# radiationsensor_r0.net
KiCad netlist of a schematic drawn in EAGLE
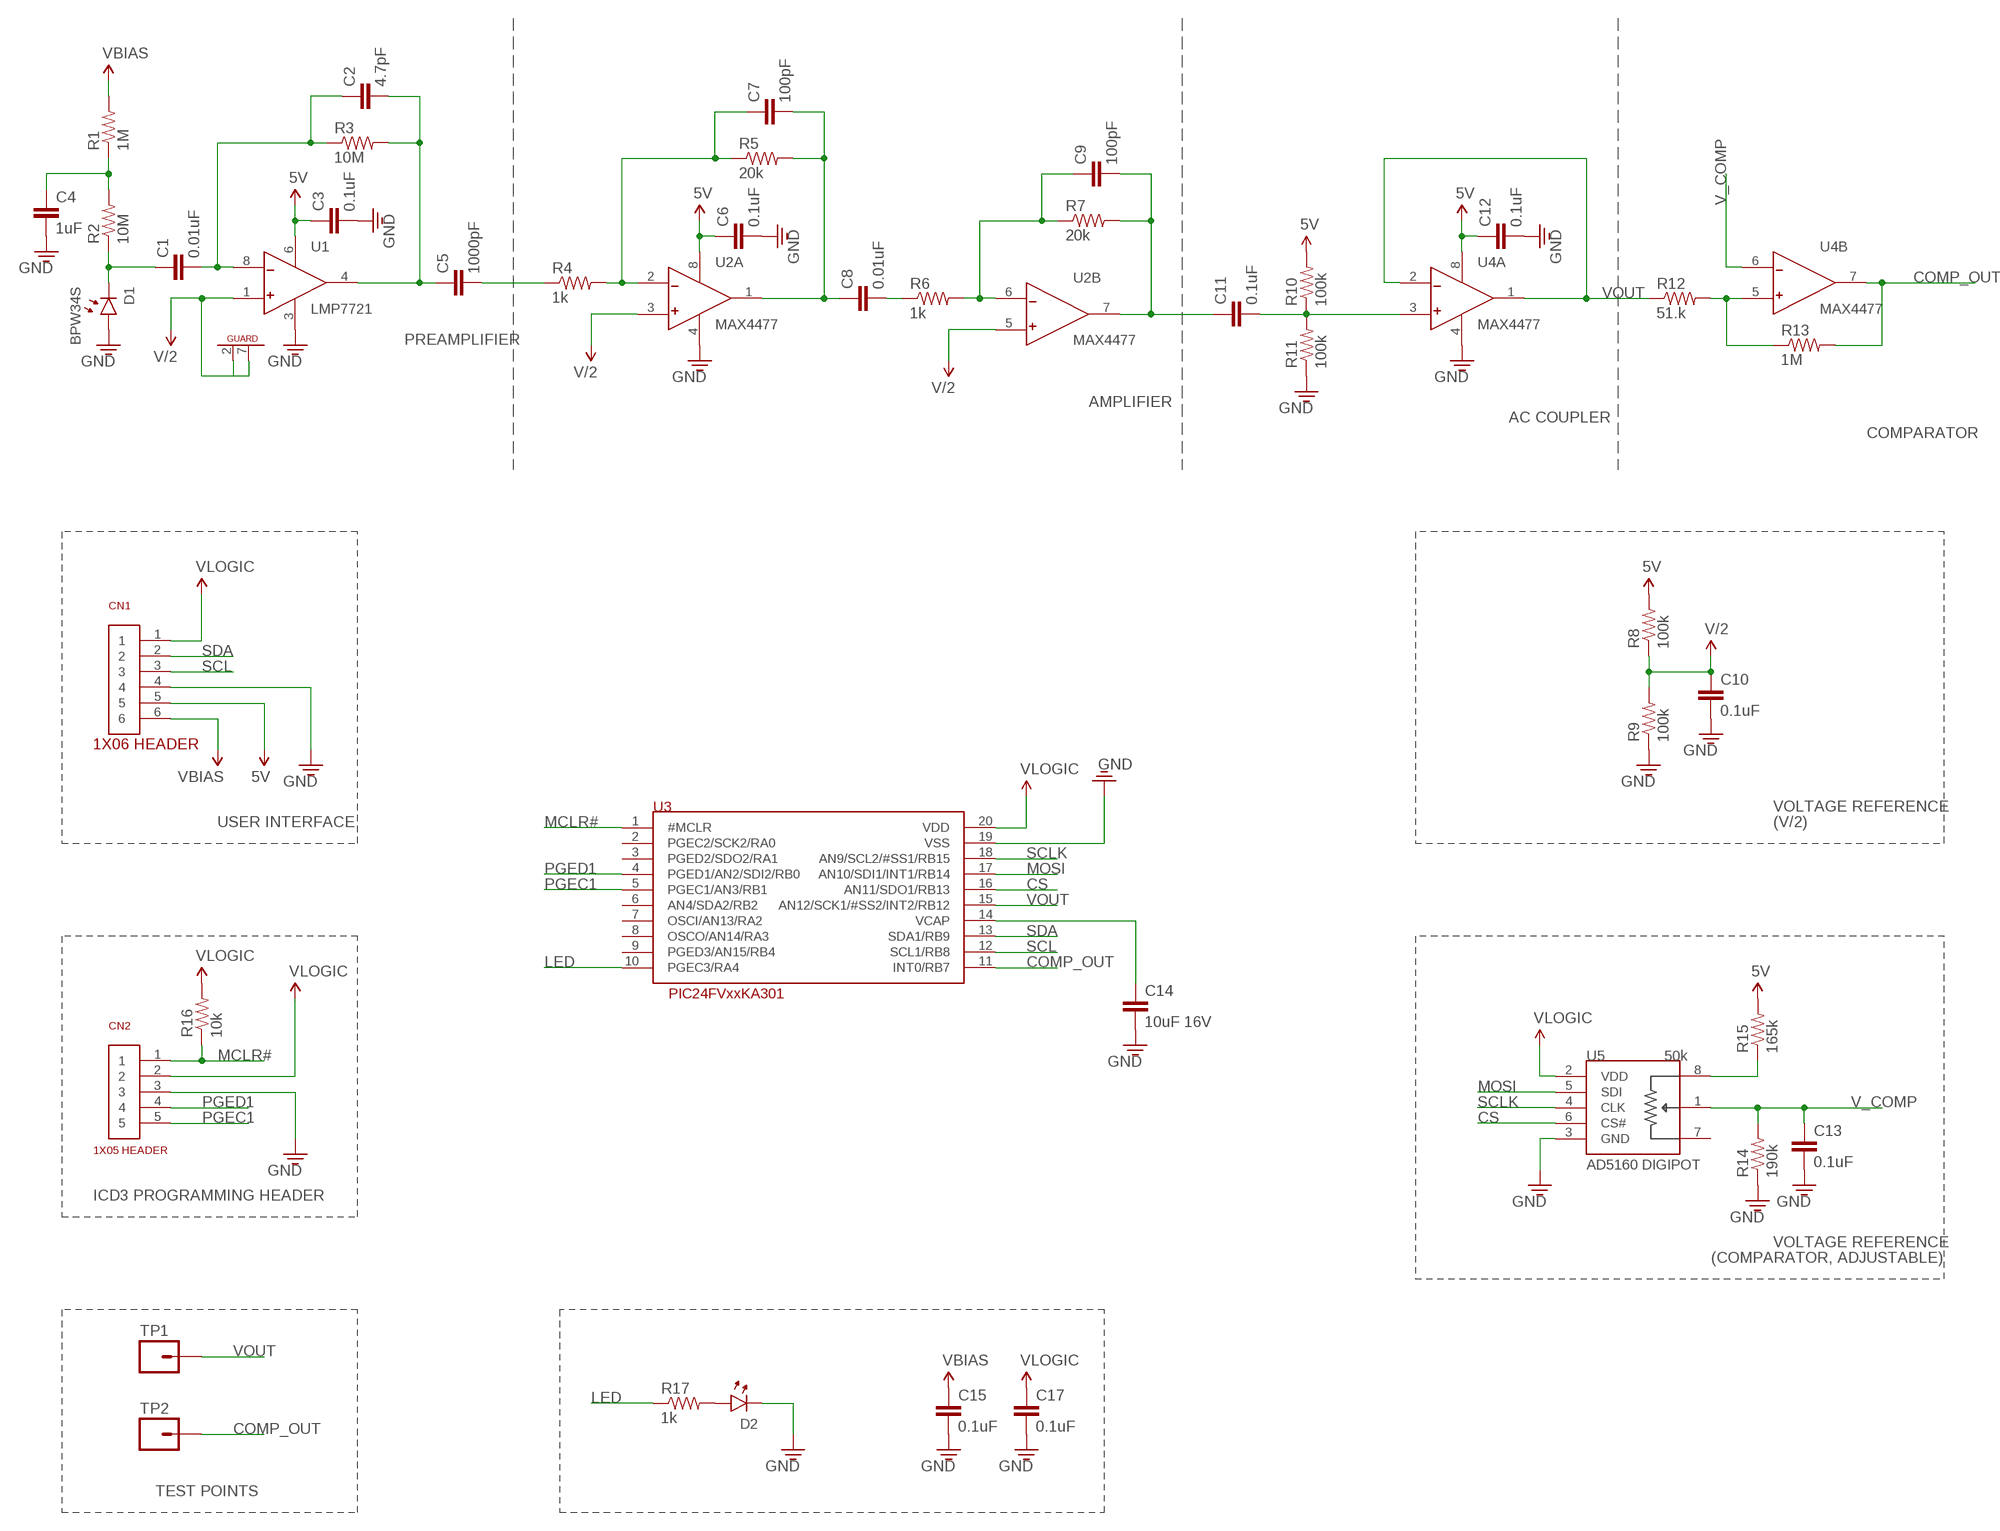
[diagram p0: schematic, sheet 1]

(export (version "E")
  (design (tool "Eeschema 10.0.6"))
  (components
    (comp (ref "C1")
      (value "0.01uF")
      (footprint "eagle-import:0603")
      (libsource (lib "eagle-import") (part "CAP0603"))
    )
    (comp (ref "C2")
      (value "4.7pF")
      (footprint "eagle-import:0603")
      (libsource (lib "eagle-import") (part "CAP0603"))
    )
    (comp (ref "C3")
      (value "0.1uF")
      (footprint "eagle-import:0603")
      (libsource (lib "eagle-import") (part "CAP0603"))
    )
    (comp (ref "C4")
      (value "1uF")
      (footprint "eagle-import:0603")
      (libsource (lib "eagle-import") (part "CAP0603"))
    )
    (comp (ref "C5")
      (value "1000pF")
      (footprint "eagle-import:0603")
      (libsource (lib "eagle-import") (part "CAP0603"))
    )
    (comp (ref "C6")
      (value "0.1uF")
      (footprint "eagle-import:0603")
      (libsource (lib "eagle-import") (part "CAP0603"))
    )
    (comp (ref "C7")
      (value "100pF")
      (footprint "eagle-import:0603")
      (libsource (lib "eagle-import") (part "CAP0603"))
    )
    (comp (ref "C8")
      (value "0.01uF")
      (footprint "eagle-import:0603")
      (libsource (lib "eagle-import") (part "CAP0603"))
    )
    (comp (ref "C9")
      (value "100pF")
      (footprint "eagle-import:0603")
      (libsource (lib "eagle-import") (part "CAP0603"))
    )
    (comp (ref "C10")
      (value "0.1uF")
      (footprint "eagle-import:0603")
      (libsource (lib "eagle-import") (part "CAP0603"))
    )
    (comp (ref "C11")
      (value "0.1uF")
      (footprint "eagle-import:0603")
      (libsource (lib "eagle-import") (part "CAP0603"))
    )
    (comp (ref "C12")
      (value "0.1uF")
      (footprint "eagle-import:0603")
      (libsource (lib "eagle-import") (part "CAP0603"))
    )
    (comp (ref "C13")
      (value "0.1uF")
      (footprint "eagle-import:0603")
      (libsource (lib "eagle-import") (part "CAP0603"))
    )
    (comp (ref "C14")
      (value "10uF 16V")
      (footprint "eagle-import:0805")
      (libsource (lib "eagle-import") (part "CAP0805"))
    )
    (comp (ref "C15")
      (value "0.1uF")
      (footprint "eagle-import:0603")
      (libsource (lib "eagle-import") (part "CAP0603"))
    )
    (comp (ref "C17")
      (value "0.1uF")
      (footprint "eagle-import:0603")
      (libsource (lib "eagle-import") (part "CAP0603"))
    )
    (comp (ref "CN1")
      (value "1X06")
      (footprint "eagle-import:1X06")
      (libsource (lib "eagle-import") (part "1X06"))
    )
    (comp (ref "CN2")
      (value "1X05")
      (footprint "eagle-import:1X05")
      (libsource (lib "eagle-import") (part "1X05"))
    )
    (comp (ref "D1")
      (value "BPW34S")
      (footprint "eagle-import:BPW34S-SIDEMOUNT")
      (libsource (lib "eagle-import") (part "PHOTODIODE"))
    )
    (comp (ref "D2")
      (value "0605-LED")
      (footprint "eagle-import:0603-LED")
      (libsource (lib "eagle-import") (part "0605-LED"))
    )
    (comp (ref "R1")
      (value "1M")
      (footprint "eagle-import:0603")
      (libsource (lib "eagle-import") (part "RESISTOR0603"))
    )
    (comp (ref "R2")
      (value "10M")
      (footprint "eagle-import:0603")
      (libsource (lib "eagle-import") (part "RESISTOR0603"))
    )
    (comp (ref "R3")
      (value "10M")
      (footprint "eagle-import:0603")
      (libsource (lib "eagle-import") (part "RESISTOR0603"))
    )
    (comp (ref "R4")
      (value "1k")
      (footprint "eagle-import:0603")
      (libsource (lib "eagle-import") (part "RESISTOR0603"))
    )
    (comp (ref "R5")
      (value "20k")
      (footprint "eagle-import:0603")
      (libsource (lib "eagle-import") (part "RESISTOR0603"))
    )
    (comp (ref "R6")
      (value "1k")
      (footprint "eagle-import:0603")
      (libsource (lib "eagle-import") (part "RESISTOR0603"))
    )
    (comp (ref "R7")
      (value "20k")
      (footprint "eagle-import:0603")
      (libsource (lib "eagle-import") (part "RESISTOR0603"))
    )
    (comp (ref "R8")
      (value "100k")
      (footprint "eagle-import:0603")
      (libsource (lib "eagle-import") (part "RESISTOR0603"))
    )
    (comp (ref "R9")
      (value "100k")
      (footprint "eagle-import:0603")
      (libsource (lib "eagle-import") (part "RESISTOR0603"))
    )
    (comp (ref "R10")
      (value "100k")
      (footprint "eagle-import:0603")
      (libsource (lib "eagle-import") (part "RESISTOR0603"))
    )
    (comp (ref "R11")
      (value "100k")
      (footprint "eagle-import:0603")
      (libsource (lib "eagle-import") (part "RESISTOR0603"))
    )
    (comp (ref "R12")
      (value "51.k")
      (footprint "eagle-import:0603")
      (libsource (lib "eagle-import") (part "RESISTOR0603"))
    )
    (comp (ref "R13")
      (value "1M")
      (footprint "eagle-import:0603")
      (libsource (lib "eagle-import") (part "RESISTOR0603"))
    )
    (comp (ref "R14")
      (value "190k")
      (footprint "eagle-import:0603")
      (libsource (lib "eagle-import") (part "RESISTOR0603"))
    )
    (comp (ref "R15")
      (value "165k")
      (footprint "eagle-import:0603")
      (libsource (lib "eagle-import") (part "RESISTOR0603"))
    )
    (comp (ref "R16")
      (value "10k")
      (footprint "eagle-import:0603")
      (libsource (lib "eagle-import") (part "RESISTOR0603"))
    )
    (comp (ref "R17")
      (value "1k")
      (footprint "eagle-import:0603")
      (libsource (lib "eagle-import") (part "RESISTOR0603"))
    )
    (comp (ref "TP1")
      (value "M01PTH")
      (footprint "eagle-import:1X01")
      (libsource (lib "eagle-import") (part "M01PTH"))
    )
    (comp (ref "TP2")
      (value "M01PTH")
      (footprint "eagle-import:1X01")
      (libsource (lib "eagle-import") (part "M01PTH"))
    )
    (comp (ref "U1")
      (value "LMP7721")
      (footprint "eagle-import:SOIC-8")
      (libsource (lib "eagle-import") (part "OPAMP-LMP7721"))
    )
    (comp (ref "U2")
      (value "MAX4477")
      (footprint "eagle-import:SOIC-8")
      (libsource (lib "eagle-import") (part "OPAMP-MAX4477"))
    )
    (comp (ref "U3")
      (value "PIC24FVXXKA301")
      (footprint "eagle-import:SOIC-20")
      (libsource (lib "eagle-import") (part "PIC24FVXXKA301"))
    )
    (comp (ref "U4")
      (value "MAX4477")
      (footprint "eagle-import:SOIC-8")
      (libsource (lib "eagle-import") (part "OPAMP-MAX4477"))
    )
    (comp (ref "U5")
      (value "50k")
      (footprint "eagle-import:SOT-23-8")
      (libsource (lib "eagle-import") (part "AD5160"))
    )
  )
  (nets
    (net (code "1") (name "/COMP_OUT") (class "Default")
      (node (ref "R13") (pin "2") (pinfunction "2_2") (pintype "passive"))
      (node (ref "TP2") (pin "1") (pinfunction "1_1") (pintype "passive"))
      (node (ref "U3") (pin "11") (pinfunction "INT0/RB7_11") (pintype "bidirectional"))
      (node (ref "U4") (pin "7") (pinfunction "OUT_7") (pintype "bidirectional"))
    )
    (net (code "2") (name "/CS") (class "Default")
      (node (ref "U3") (pin "16") (pinfunction "AN11/SDO1/RB13_16") (pintype "bidirectional"))
      (node (ref "U5") (pin "6") (pinfunction "CS#_6") (pintype "bidirectional"))
    )
    (net (code "3") (name "/LED") (class "Default")
      (node (ref "R17") (pin "1") (pinfunction "1_1") (pintype "passive"))
      (node (ref "U3") (pin "10") (pinfunction "PGEC3/RA4_10") (pintype "bidirectional"))
    )
    (net (code "4") (name "/MCLR#") (class "Default")
      (node (ref "CN2") (pin "1") (pinfunction "1_1") (pintype "bidirectional"))
      (node (ref "R16") (pin "1") (pinfunction "1_1") (pintype "passive"))
      (node (ref "U3") (pin "1") (pinfunction "#MCLR_1") (pintype "bidirectional"))
    )
    (net (code "5") (name "/MOSI") (class "Default")
      (node (ref "U3") (pin "17") (pinfunction "AN10/SDI1/INT1/RB14_17") (pintype "bidirectional"))
      (node (ref "U5") (pin "5") (pinfunction "SDI_5") (pintype "bidirectional"))
    )
    (net (code "6") (name "/PGEC1") (class "Default")
      (node (ref "CN2") (pin "5") (pinfunction "5_5") (pintype "bidirectional"))
      (node (ref "U3") (pin "5") (pinfunction "PGEC1/AN3/RB1_5") (pintype "bidirectional"))
    )
    (net (code "7") (name "/PGED1") (class "Default")
      (node (ref "CN2") (pin "4") (pinfunction "4_4") (pintype "bidirectional"))
      (node (ref "U3") (pin "4") (pinfunction "PGED1/AN2/SDI2/RB0_4") (pintype "bidirectional"))
    )
    (net (code "8") (name "/SCL") (class "Default")
      (node (ref "CN1") (pin "3") (pinfunction "3_3") (pintype "bidirectional"))
      (node (ref "U3") (pin "12") (pinfunction "SCL1/RB8_12") (pintype "bidirectional"))
    )
    (net (code "9") (name "/SCLK") (class "Default")
      (node (ref "U3") (pin "18") (pinfunction "AN9/SCL2/#SS1/RB15_18") (pintype "bidirectional"))
      (node (ref "U5") (pin "4") (pinfunction "CLK_4") (pintype "bidirectional"))
    )
    (net (code "10") (name "/SDA") (class "Default")
      (node (ref "CN1") (pin "2") (pinfunction "2_2") (pintype "bidirectional"))
      (node (ref "U3") (pin "13") (pinfunction "SDA1/RB9_13") (pintype "bidirectional"))
    )
    (net (code "11") (name "/VOUT") (class "Default")
      (node (ref "R12") (pin "1") (pinfunction "1_1") (pintype "passive"))
      (node (ref "TP1") (pin "1") (pinfunction "1_1") (pintype "passive"))
      (node (ref "U3") (pin "15") (pinfunction "AN12/SCK1/#SS2/INT2/RB12_15") (pintype "bidirectional"))
      (node (ref "U4") (pin "1") (pinfunction "OUT_1") (pintype "bidirectional"))
      (node (ref "U4") (pin "2") (pinfunction "-_2") (pintype "bidirectional"))
    )
    (net (code "12") (name "/V_COMP") (class "Default")
      (node (ref "C13") (pin "1") (pinfunction "1_1") (pintype "passive"))
      (node (ref "R14") (pin "2") (pinfunction "2_2") (pintype "passive"))
      (node (ref "U4") (pin "6") (pinfunction "-_6") (pintype "bidirectional"))
      (node (ref "U5") (pin "1") (pinfunction "W_1") (pintype "bidirectional"))
    )
    (net (code "13") (name "5V") (class "Default")
      (node (ref "C12") (pin "1") (pinfunction "1_1") (pintype "passive"))
      (node (ref "C3") (pin "1") (pinfunction "1_1") (pintype "passive"))
      (node (ref "C6") (pin "1") (pinfunction "1_1") (pintype "passive"))
      (node (ref "CN1") (pin "5") (pinfunction "5_5") (pintype "bidirectional"))
      (node (ref "R10") (pin "2") (pinfunction "2_2") (pintype "passive"))
      (node (ref "R15") (pin "2") (pinfunction "2_2") (pintype "passive"))
      (node (ref "R8") (pin "2") (pinfunction "2_2") (pintype "passive"))
      (node (ref "U1") (pin "6") (pinfunction "VCC_6") (pintype "bidirectional"))
      (node (ref "U2") (pin "8") (pinfunction "V+_8") (pintype "bidirectional"))
      (node (ref "U4") (pin "8") (pinfunction "V+_8") (pintype "bidirectional"))
    )
    (net (code "14") (name "GND") (class "Default")
      (node (ref "C10") (pin "2") (pinfunction "2_2") (pintype "passive"))
      (node (ref "C12") (pin "2") (pinfunction "2_2") (pintype "passive"))
      (node (ref "C13") (pin "2") (pinfunction "2_2") (pintype "passive"))
      (node (ref "C14") (pin "2") (pinfunction "2_2") (pintype "passive"))
      (node (ref "C15") (pin "2") (pinfunction "2_2") (pintype "passive"))
      (node (ref "C17") (pin "2") (pinfunction "2_2") (pintype "passive"))
      (node (ref "C3") (pin "2") (pinfunction "2_2") (pintype "passive"))
      (node (ref "C4") (pin "2") (pinfunction "2_2") (pintype "passive"))
      (node (ref "C6") (pin "2") (pinfunction "2_2") (pintype "passive"))
      (node (ref "CN1") (pin "4") (pinfunction "4_4") (pintype "bidirectional"))
      (node (ref "CN2") (pin "3") (pinfunction "3_3") (pintype "bidirectional"))
      (node (ref "D1") (pin "A") (pinfunction "ANODE_A") (pintype "bidirectional"))
      (node (ref "D2") (pin "CATHODE") (pinfunction "CATHODE_CATHODE") (pintype "bidirectional"))
      (node (ref "R11") (pin "1") (pinfunction "1_1") (pintype "passive"))
      (node (ref "R14") (pin "1") (pinfunction "1_1") (pintype "passive"))
      (node (ref "R9") (pin "1") (pinfunction "1_1") (pintype "passive"))
      (node (ref "U1") (pin "3") (pinfunction "GND_3") (pintype "bidirectional"))
      (node (ref "U2") (pin "4") (pinfunction "V-_4") (pintype "bidirectional"))
      (node (ref "U3") (pin "19") (pinfunction "VSS_19") (pintype "bidirectional"))
      (node (ref "U4") (pin "4") (pinfunction "V-_4") (pintype "bidirectional"))
      (node (ref "U5") (pin "3") (pinfunction "GND_3") (pintype "bidirectional"))
    )
    (net (code "15") (name "Net-(C4-Pad1)") (class "Default")
      (node (ref "C4") (pin "1") (pinfunction "1_1") (pintype "passive"))
      (node (ref "R1") (pin "1") (pinfunction "1_1") (pintype "passive"))
      (node (ref "R2") (pin "2") (pinfunction "2_2") (pintype "passive"))
    )
    (net (code "16") (name "Net-(C5-Pad2)") (class "Default")
      (node (ref "C5") (pin "2") (pinfunction "2_2") (pintype "passive"))
      (node (ref "R4") (pin "1") (pinfunction "1_1") (pintype "passive"))
    )
    (net (code "17") (name "Net-(C8-Pad2)") (class "Default")
      (node (ref "C8") (pin "2") (pinfunction "2_2") (pintype "passive"))
      (node (ref "R6") (pin "1") (pinfunction "1_1") (pintype "passive"))
    )
    (net (code "18") (name "Net-(D1-CATHODE)") (class "Default")
      (node (ref "C1") (pin "1") (pinfunction "1_1") (pintype "passive"))
      (node (ref "D1") (pin "C") (pinfunction "CATHODE_C") (pintype "bidirectional"))
      (node (ref "R2") (pin "1") (pinfunction "1_1") (pintype "passive"))
    )
    (net (code "19") (name "Net-(D2-PadANODE)") (class "Default")
      (node (ref "D2") (pin "ANODE") (pinfunction "ANODE_ANODE") (pintype "bidirectional"))
      (node (ref "R17") (pin "2") (pinfunction "2_2") (pintype "passive"))
    )
    (net (code "20") (name "Net-(U1--)") (class "Default")
      (node (ref "C1") (pin "2") (pinfunction "2_2") (pintype "passive"))
      (node (ref "C2") (pin "1") (pinfunction "1_1") (pintype "passive"))
      (node (ref "R3") (pin "1") (pinfunction "1_1") (pintype "passive"))
      (node (ref "U1") (pin "8") (pinfunction "-_8") (pintype "bidirectional"))
    )
    (net (code "21") (name "Net-(U1-OUT)") (class "Default")
      (node (ref "C2") (pin "2") (pinfunction "2_2") (pintype "passive"))
      (node (ref "C5") (pin "1") (pinfunction "1_1") (pintype "passive"))
      (node (ref "R3") (pin "2") (pinfunction "2_2") (pintype "passive"))
      (node (ref "U1") (pin "4") (pinfunction "OUT_4") (pintype "bidirectional"))
    )
    (net (code "22") (name "Net-(U2A--)") (class "Default")
      (node (ref "C7") (pin "1") (pinfunction "1_1") (pintype "passive"))
      (node (ref "R4") (pin "2") (pinfunction "2_2") (pintype "passive"))
      (node (ref "R5") (pin "1") (pinfunction "1_1") (pintype "passive"))
      (node (ref "U2") (pin "2") (pinfunction "-_2") (pintype "bidirectional"))
    )
    (net (code "23") (name "Net-(U2A-OUT)") (class "Default")
      (node (ref "C7") (pin "2") (pinfunction "2_2") (pintype "passive"))
      (node (ref "C8") (pin "1") (pinfunction "1_1") (pintype "passive"))
      (node (ref "R5") (pin "2") (pinfunction "2_2") (pintype "passive"))
      (node (ref "U2") (pin "1") (pinfunction "OUT_1") (pintype "bidirectional"))
    )
    (net (code "24") (name "Net-(U2B--)") (class "Default")
      (node (ref "C9") (pin "1") (pinfunction "1_1") (pintype "passive"))
      (node (ref "R6") (pin "2") (pinfunction "2_2") (pintype "passive"))
      (node (ref "R7") (pin "1") (pinfunction "1_1") (pintype "passive"))
      (node (ref "U2") (pin "6") (pinfunction "-_6") (pintype "bidirectional"))
    )
    (net (code "25") (name "Net-(U2B-OUT)") (class "Default")
      (node (ref "C11") (pin "1") (pinfunction "1_1") (pintype "passive"))
      (node (ref "C9") (pin "2") (pinfunction "2_2") (pintype "passive"))
      (node (ref "R7") (pin "2") (pinfunction "2_2") (pintype "passive"))
      (node (ref "U2") (pin "7") (pinfunction "OUT_7") (pintype "bidirectional"))
    )
    (net (code "26") (name "Net-(U3-VCAP)") (class "Default")
      (node (ref "C14") (pin "1") (pinfunction "1_1") (pintype "passive"))
      (node (ref "U3") (pin "14") (pinfunction "VCAP_14") (pintype "bidirectional"))
    )
    (net (code "27") (name "Net-(U4A-+)") (class "Default")
      (node (ref "C11") (pin "2") (pinfunction "2_2") (pintype "passive"))
      (node (ref "R10") (pin "1") (pinfunction "1_1") (pintype "passive"))
      (node (ref "R11") (pin "2") (pinfunction "2_2") (pintype "passive"))
      (node (ref "U4") (pin "3") (pinfunction "+_3") (pintype "bidirectional"))
    )
    (net (code "28") (name "Net-(U4B-+)") (class "Default")
      (node (ref "R12") (pin "2") (pinfunction "2_2") (pintype "passive"))
      (node (ref "R13") (pin "1") (pinfunction "1_1") (pintype "passive"))
      (node (ref "U4") (pin "5") (pinfunction "+_5") (pintype "bidirectional"))
    )
    (net (code "29") (name "Net-(U5-A)") (class "Default")
      (node (ref "R15") (pin "1") (pinfunction "1_1") (pintype "passive"))
      (node (ref "U5") (pin "8") (pinfunction "A_8") (pintype "bidirectional"))
    )
    (net (code "30") (name "VBIAS") (class "Default")
      (node (ref "C15") (pin "1") (pinfunction "1_1") (pintype "passive"))
      (node (ref "CN1") (pin "6") (pinfunction "6_6") (pintype "bidirectional"))
      (node (ref "R1") (pin "2") (pinfunction "2_2") (pintype "passive"))
    )
    (net (code "31") (name "VLOGIC") (class "Default")
      (node (ref "C17") (pin "1") (pinfunction "1_1") (pintype "passive"))
      (node (ref "CN1") (pin "1") (pinfunction "1_1") (pintype "bidirectional"))
      (node (ref "CN2") (pin "2") (pinfunction "2_2") (pintype "bidirectional"))
      (node (ref "R16") (pin "2") (pinfunction "2_2") (pintype "passive"))
      (node (ref "U3") (pin "20") (pinfunction "VDD_20") (pintype "bidirectional"))
      (node (ref "U5") (pin "2") (pinfunction "VDD_2") (pintype "bidirectional"))
    )
    (net (code "32") (name "V{slash}2") (class "Default")
      (node (ref "C10") (pin "1") (pinfunction "1_1") (pintype "passive"))
      (node (ref "R8") (pin "1") (pinfunction "1_1") (pintype "passive"))
      (node (ref "R9") (pin "2") (pinfunction "2_2") (pintype "passive"))
      (node (ref "U1") (pin "1") (pinfunction "+_1") (pintype "bidirectional"))
      (node (ref "U1") (pin "2") (pinfunction "G1_2") (pintype "bidirectional"))
      (node (ref "U1") (pin "7") (pinfunction "G2_7") (pintype "bidirectional"))
      (node (ref "U2") (pin "3") (pinfunction "+_3") (pintype "bidirectional"))
      (node (ref "U2") (pin "5") (pinfunction "+_5") (pintype "bidirectional"))
    )
    (net (code "33") (name "unconnected-(U3-AN4{slash}SDA2{slash}RB2-Pad6)") (class "Default")
      (node (ref "U3") (pin "6") (pinfunction "AN4/SDA2/RB2_6") (pintype "bidirectional"))
    )
    (net (code "34") (name "unconnected-(U3-OSCI{slash}AN13{slash}RA2-Pad7)") (class "Default")
      (node (ref "U3") (pin "7") (pinfunction "OSCI/AN13/RA2_7") (pintype "bidirectional"))
    )
    (net (code "35") (name "unconnected-(U3-OSCO{slash}AN14{slash}RA3-Pad8)") (class "Default")
      (node (ref "U3") (pin "8") (pinfunction "OSCO/AN14/RA3_8") (pintype "bidirectional"))
    )
    (net (code "36") (name "unconnected-(U3-PGEC2{slash}SCK2{slash}RA0-Pad2)") (class "Default")
      (node (ref "U3") (pin "2") (pinfunction "PGEC2/SCK2/RA0_2") (pintype "bidirectional"))
    )
    (net (code "37") (name "unconnected-(U3-PGED2{slash}SDO2{slash}RA1-Pad3)") (class "Default")
      (node (ref "U3") (pin "3") (pinfunction "PGED2/SDO2/RA1_3") (pintype "bidirectional"))
    )
    (net (code "38") (name "unconnected-(U3-PGED3{slash}AN15{slash}RB4-Pad9)") (class "Default")
      (node (ref "U3") (pin "9") (pinfunction "PGED3/AN15/RB4_9") (pintype "bidirectional"))
    )
    (net (code "39") (name "unconnected-(U5-B-Pad7)") (class "Default")
      (node (ref "U5") (pin "7") (pinfunction "B_7") (pintype "bidirectional"))
    )
  )
)
